# 280049_tester_board.net
KiCad netlist of a schematic drawn in Altium Designer
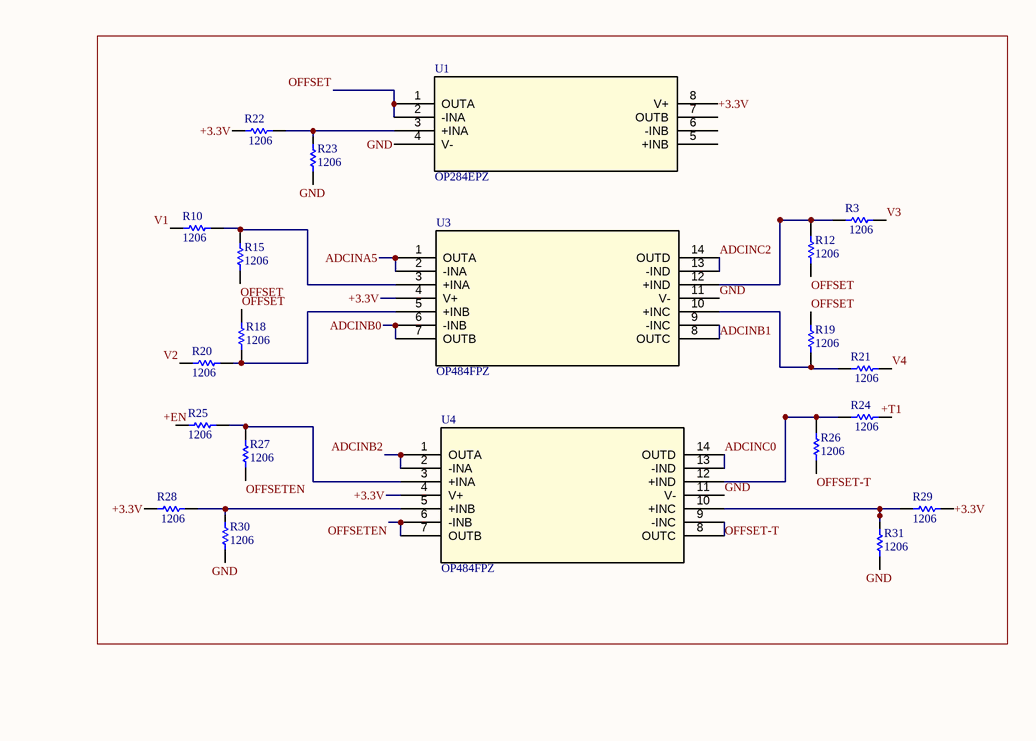
[diagram p0: 280049 tester board.SchDoc, top left]
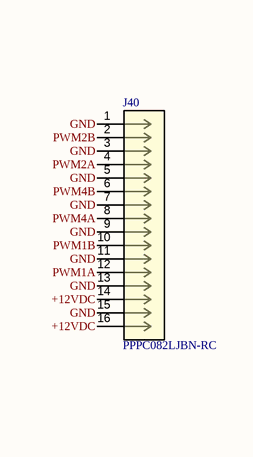
[diagram p1: 280049 tester board.SchDoc, top right]
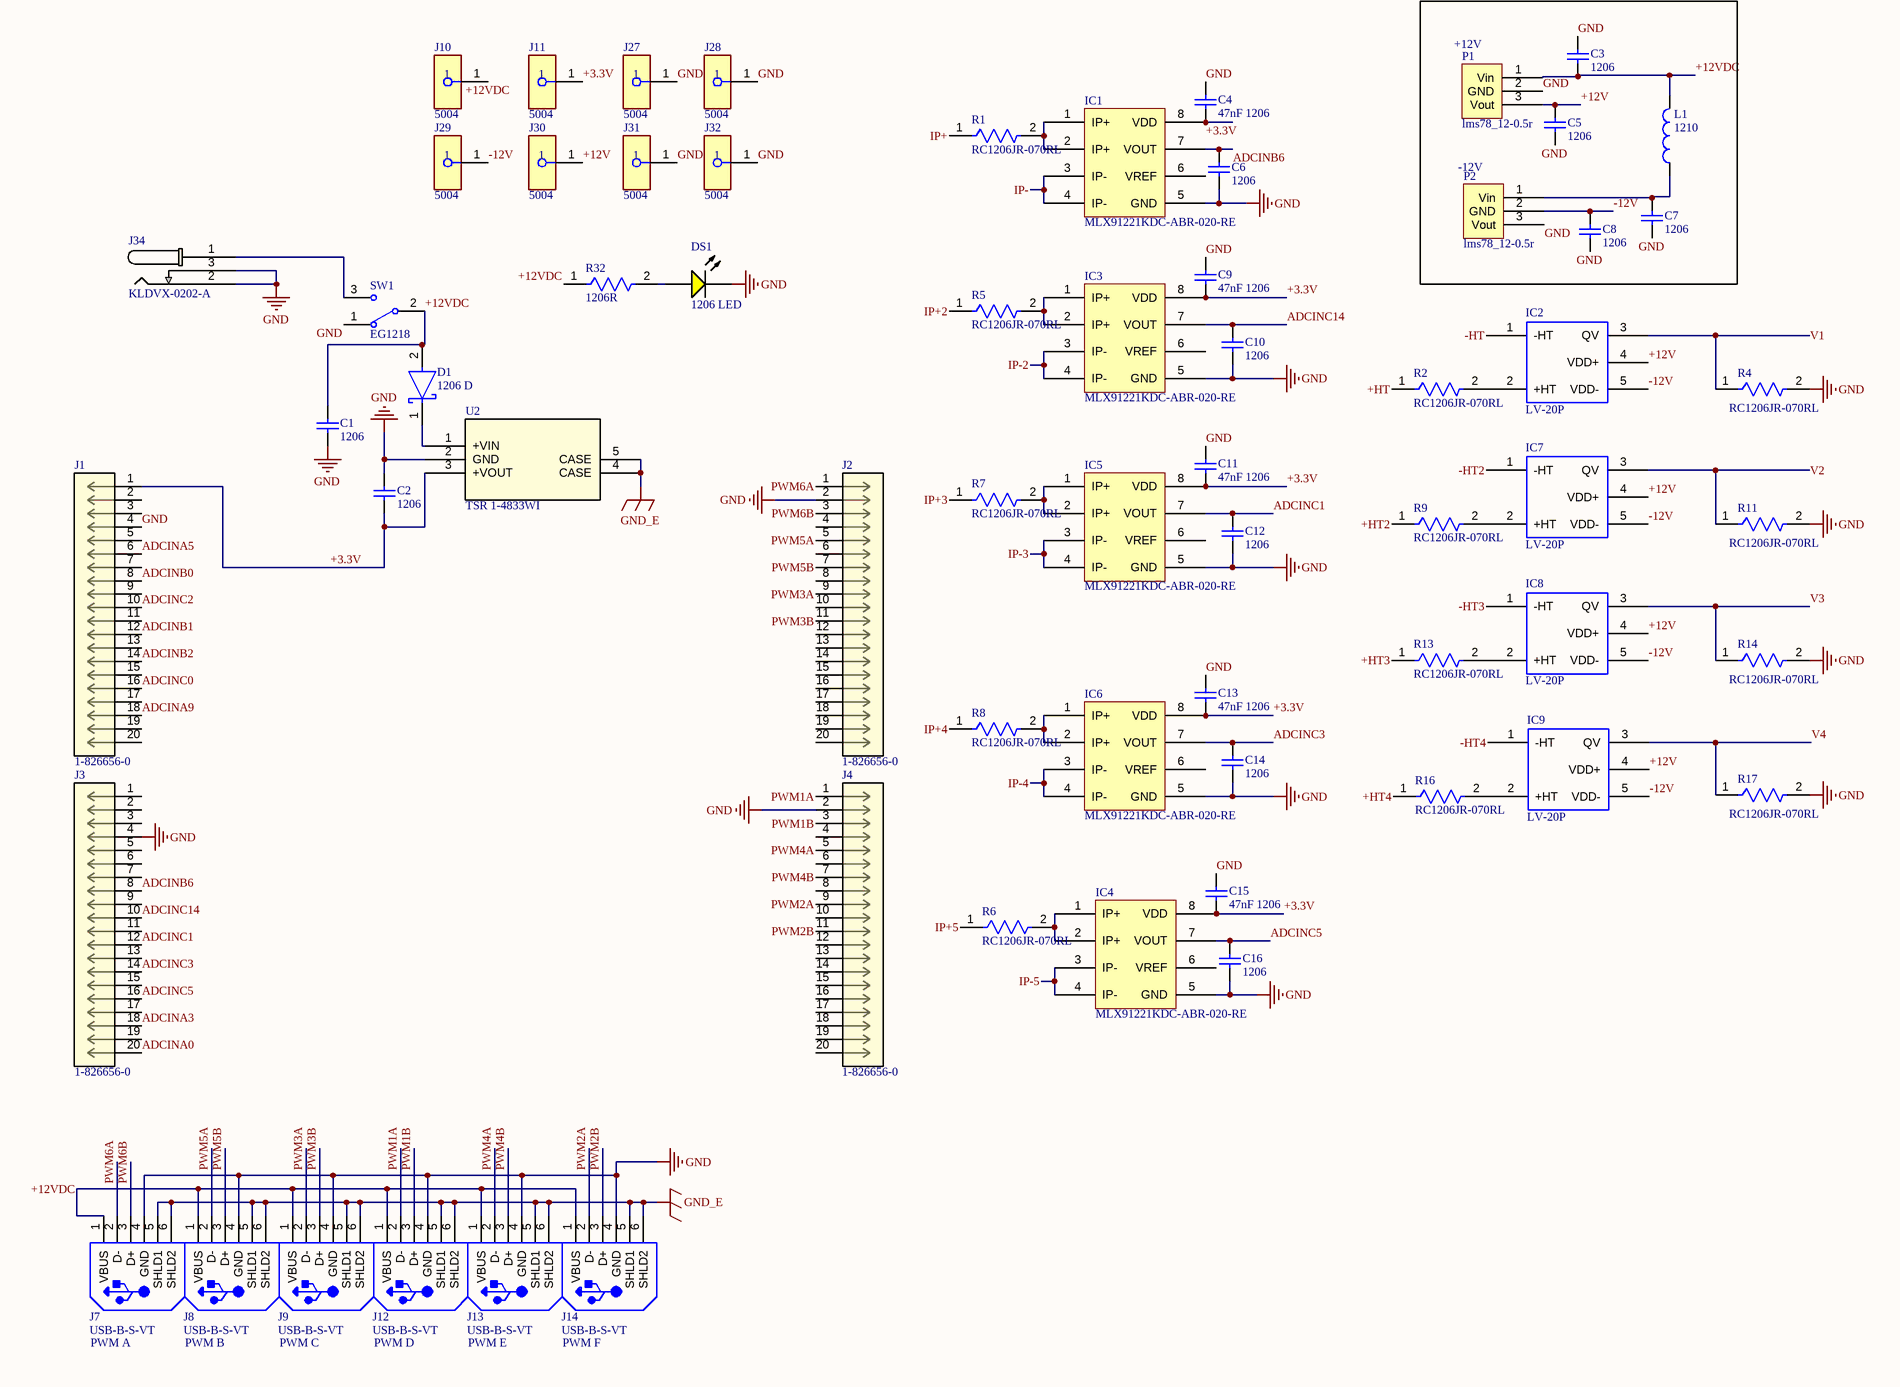
[diagram p2: 280049 tester board.SchDoc, bottom left]
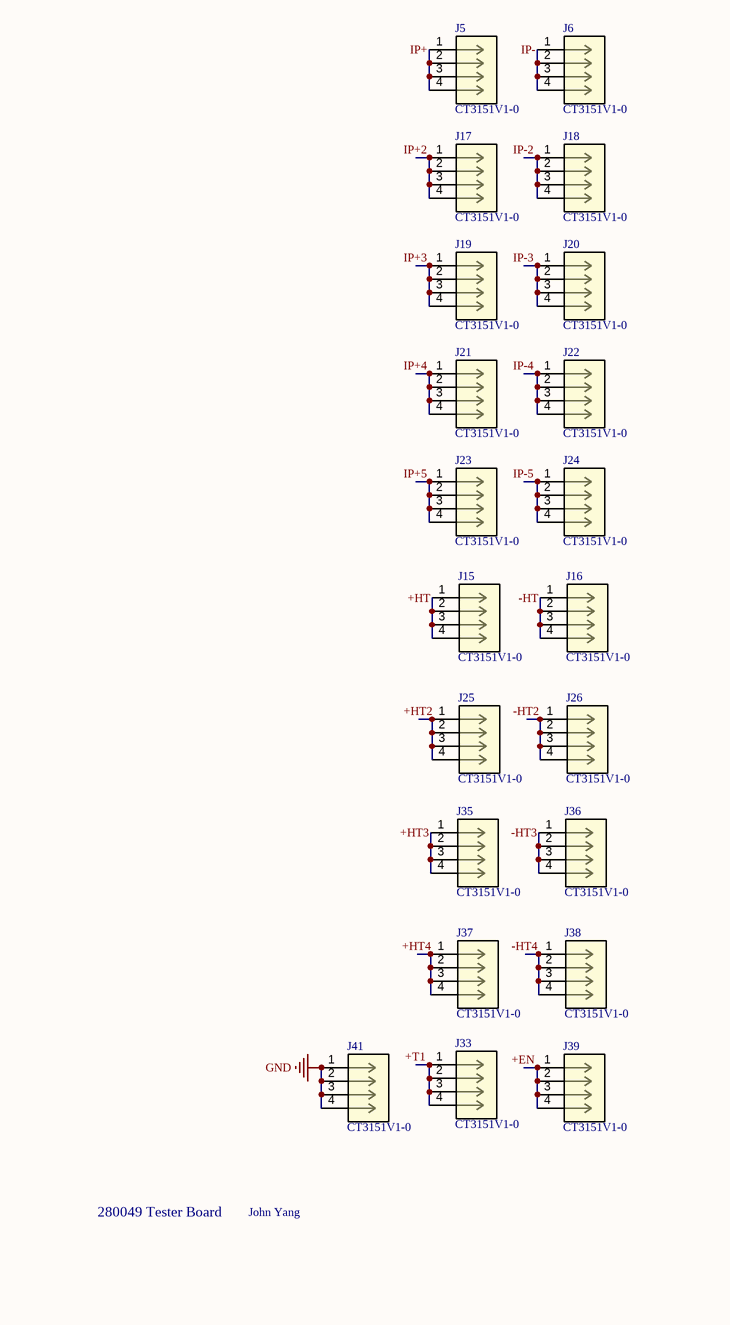
[diagram p3: 280049 tester board.SchDoc, bottom right]

(export (version "E")
  (design (tool "Eeschema 10.0.6"))
  (components
    (comp (ref "C1")
      (value "1206")
      (footprint "CAPC1206(3216)130_M")
      (description "CAP 47nF 200V ±10% 1206 (3216 Metric) Thickness 1.3mm SMD")
      (fields (field (name "TOLERANCE") "Â±10%"))
      (libsource (lib "Altium Content Vault") (part "CAP"))
    )
    (comp (ref "C2")
      (value "1206")
      (footprint "CAPC1206(3216)130_M")
      (description "CAP 47nF 200V ±10% 1206 (3216 Metric) Thickness 1.3mm SMD")
      (fields (field (name "TOLERANCE") "Â±10%"))
      (libsource (lib "Altium Content Vault") (part "CAP"))
    )
    (comp (ref "C3")
      (value "1206")
      (footprint "CAPC1206(3216)130_M")
      (description "CAP 47nF 200V ±10% 1206 (3216 Metric) Thickness 1.3mm SMD")
      (fields (field (name "TOLERANCE") "Â±10%"))
      (libsource (lib "Altium Content Vault") (part "CAP"))
    )
    (comp (ref "C4")
      (value "47nF 1206")
      (footprint "CAPC1206(3216)130_M")
      (description "CAP 47nF 200V ±10% 1206 (3216 Metric) Thickness 1.3mm SMD")
      (fields (field (name "TOLERANCE") "Â±10%"))
      (libsource (lib "Altium Content Vault") (part "CAP"))
    )
    (comp (ref "C5")
      (value "1206")
      (footprint "CAPC1206(3216)130_M")
      (description "CAP 47nF 200V ±10% 1206 (3216 Metric) Thickness 1.3mm SMD")
      (fields (field (name "TOLERANCE") "Â±10%"))
      (libsource (lib "Altium Content Vault") (part "CAP"))
    )
    (comp (ref "C6")
      (value "1206")
      (footprint "CAPC1206(3216)130_M")
      (description "CAP 47nF 200V ±10% 1206 (3216 Metric) Thickness 1.3mm SMD")
      (fields (field (name "TOLERANCE") "Â±10%"))
      (libsource (lib "Altium Content Vault") (part "CAP"))
    )
    (comp (ref "C7")
      (value "1206")
      (footprint "CAPC1206(3216)130_M")
      (description "CAP 47nF 200V ±10% 1206 (3216 Metric) Thickness 1.3mm SMD")
      (fields (field (name "TOLERANCE") "Â±10%"))
      (libsource (lib "Altium Content Vault") (part "CAP"))
    )
    (comp (ref "C8")
      (value "1206")
      (footprint "CAPC1206(3216)130_M")
      (description "CAP 47nF 200V ±10% 1206 (3216 Metric) Thickness 1.3mm SMD")
      (fields (field (name "TOLERANCE") "Â±10%"))
      (libsource (lib "Altium Content Vault") (part "CAP"))
    )
    (comp (ref "C9")
      (value "47nF 1206")
      (footprint "CAPC1206(3216)130_M")
      (description "CAP 47nF 200V ±10% 1206 (3216 Metric) Thickness 1.3mm SMD")
      (fields (field (name "TOLERANCE") "Â±10%"))
      (libsource (lib "Altium Content Vault") (part "CAP"))
    )
    (comp (ref "C10")
      (value "1206")
      (footprint "CAPC1206(3216)130_M")
      (description "CAP 47nF 200V ±10% 1206 (3216 Metric) Thickness 1.3mm SMD")
      (fields (field (name "TOLERANCE") "Â±10%"))
      (libsource (lib "Altium Content Vault") (part "CAP"))
    )
    (comp (ref "C11")
      (value "47nF 1206")
      (footprint "CAPC1206(3216)130_M")
      (description "CAP 47nF 200V ±10% 1206 (3216 Metric) Thickness 1.3mm SMD")
      (fields (field (name "TOLERANCE") "Â±10%"))
      (libsource (lib "Altium Content Vault") (part "CAP"))
    )
    (comp (ref "C12")
      (value "1206")
      (footprint "CAPC1206(3216)130_M")
      (description "CAP 47nF 200V ±10% 1206 (3216 Metric) Thickness 1.3mm SMD")
      (fields (field (name "TOLERANCE") "Â±10%"))
      (libsource (lib "Altium Content Vault") (part "CAP"))
    )
    (comp (ref "C13")
      (value "47nF 1206")
      (footprint "CAPC1206(3216)130_M")
      (description "CAP 47nF 200V ±10% 1206 (3216 Metric) Thickness 1.3mm SMD")
      (fields (field (name "TOLERANCE") "Â±10%"))
      (libsource (lib "Altium Content Vault") (part "CAP"))
    )
    (comp (ref "C14")
      (value "1206")
      (footprint "CAPC1206(3216)130_M")
      (description "CAP 47nF 200V ±10% 1206 (3216 Metric) Thickness 1.3mm SMD")
      (fields (field (name "TOLERANCE") "Â±10%"))
      (libsource (lib "Altium Content Vault") (part "CAP"))
    )
    (comp (ref "C15")
      (value "47nF 1206")
      (footprint "CAPC1206(3216)130_M")
      (description "CAP 47nF 200V ±10% 1206 (3216 Metric) Thickness 1.3mm SMD")
      (fields (field (name "TOLERANCE") "Â±10%"))
      (libsource (lib "Altium Content Vault") (part "CAP"))
    )
    (comp (ref "C16")
      (value "1206")
      (footprint "CAPC1206(3216)130_M")
      (description "CAP 47nF 200V ±10% 1206 (3216 Metric) Thickness 1.3mm SMD")
      (fields (field (name "TOLERANCE") "Â±10%"))
      (libsource (lib "Altium Content Vault") (part "CAP"))
    )
    (comp (ref "D1")
      (value "1206 D")
      (footprint "FP-SD1206S-MFG")
      (description "DIODE SCHOTTKY 40V 2A 1206")
      (fields (field (name "MANUFACTURER PART NUMBER") "SD1206S040S2R0") (field (name "MANUFACTURER") "AVX"))
      (libsource (lib "Altium Content Vault") (part "1d6ec82d83fb6aee721767c19dac4b9"))
    )
    (comp (ref "DS1")
      (value "1206 LED")
      (footprint "LUMX-SML-LX1206YC-TR_V")
      (description "Yellow LED, Water Clear Len, 585 nm, 2.1 V, -40 to 85 degC, 2-Pin SMD, RoHS, Tape and Reel")
      (fields (field (name "MANUFACTURER") "Lumex"))
      (libsource (lib "Altium Content Vault") (part "LED-YELLOW-AK-2"))
    )
    (comp (ref "IC1")
      (value "MLX91221KDC-ABR-020-RE")
      (footprint "MLX91221KDC-ABR-020-RE")
      (description ".088 W")
      (libsource (lib "John Yang") (part "MLX91221KDC-ABR-020-RE"))
    )
    (comp (ref "IC2")
      (value "LV-20P")
      (footprint "LV-20P")
      (description "0.15 W")
      (libsource (lib "LV-20P") (part "LV-20P"))
    )
    (comp (ref "IC3")
      (value "MLX91221KDC-ABR-020-RE")
      (footprint "MLX91221KDC-ABR-020-RE")
      (description ".088 W")
      (libsource (lib "John Yang") (part "MLX91221KDC-ABR-020-RE"))
    )
    (comp (ref "IC4")
      (value "MLX91221KDC-ABR-020-RE")
      (footprint "MLX91221KDC-ABR-020-RE")
      (description ".088 W")
      (libsource (lib "John Yang") (part "MLX91221KDC-ABR-020-RE"))
    )
    (comp (ref "IC5")
      (value "MLX91221KDC-ABR-020-RE")
      (footprint "MLX91221KDC-ABR-020-RE")
      (description ".088 W")
      (libsource (lib "John Yang") (part "MLX91221KDC-ABR-020-RE"))
    )
    (comp (ref "IC6")
      (value "MLX91221KDC-ABR-020-RE")
      (footprint "MLX91221KDC-ABR-020-RE")
      (description ".088 W")
      (libsource (lib "John Yang") (part "MLX91221KDC-ABR-020-RE"))
    )
    (comp (ref "IC7")
      (value "LV-20P")
      (footprint "LV-20P")
      (description "0.15 W")
      (libsource (lib "LV-20P") (part "LV-20P"))
    )
    (comp (ref "IC8")
      (value "LV-20P")
      (footprint "LV-20P")
      (description "0.15 W")
      (libsource (lib "LV-20P") (part "LV-20P"))
    )
    (comp (ref "IC9")
      (value "LV-20P")
      (footprint "LV-20P")
      (description "0.15 W")
      (libsource (lib "LV-20P") (part "LV-20P"))
    )
    (comp (ref "J1")
      (value "1-826656-0")
      (footprint "CON20_2X10_P100UM_HDR_TYC")
      (description "No Description Available")
      (libsource (lib "John Yang") (part "1-826656-0"))
    )
    (comp (ref "J2")
      (value "1-826656-0")
      (footprint "CON20_2X10_P100UM_HDR_TYC")
      (description "No Description Available")
      (libsource (lib "John Yang") (part "1-826656-0"))
    )
    (comp (ref "J3")
      (value "1-826656-0")
      (footprint "CON20_2X10_P100UM_HDR_TYC")
      (description "No Description Available")
      (libsource (lib "John Yang") (part "1-826656-0"))
    )
    (comp (ref "J4")
      (value "1-826656-0")
      (footprint "CON20_2X10_P100UM_HDR_TYC")
      (description "No Description Available")
      (libsource (lib "John Yang") (part "1-826656-0"))
    )
    (comp (ref "J5")
      (value "CT3151V1-0")
      (footprint "CON4_CT3151V1-0_CTE")
      (description "No Description Available")
      (fields (field (name "COPYRIGHT") "Copyright (C) 2024 Ultra Librarian. All rights reserved."))
      (libsource (lib "John Yang") (part "CT3151V1-0"))
    )
    (comp (ref "J6")
      (value "CT3151V1-0")
      (footprint "CON4_CT3151V1-0_CTE")
      (description "No Description Available")
      (fields (field (name "COPYRIGHT") "Copyright (C) 2024 Ultra Librarian. All rights reserved."))
      (libsource (lib "John Yang") (part "CT3151V1-0"))
    )
    (comp (ref "J7")
      (value "PWM A")
      (footprint "CONN4_5787834-1_TEC")
      (description "USB TYPE B SINGLE VERTICAL")
      (fields (field (name "MANUFACTURER") "Adam Tech") (field (name "SUPPLIER PART NUMBER 1") "USB-B-S-VT"))
      (libsource (lib "ECE 512 Breadboard Modular system") (part "CONN_USB_TypeB"))
    )
    (comp (ref "J8")
      (value "PWM B")
      (footprint "CONN4_5787834-1_TEC")
      (description "USB TYPE B SINGLE VERTICAL")
      (fields (field (name "MANUFACTURER") "Adam Tech") (field (name "SUPPLIER PART NUMBER 1") "USB-B-S-VT"))
      (libsource (lib "ECE 512 Breadboard Modular system") (part "CONN_USB_TypeB"))
    )
    (comp (ref "J9")
      (value "PWM C")
      (footprint "CONN4_5787834-1_TEC")
      (description "USB TYPE B SINGLE VERTICAL")
      (fields (field (name "MANUFACTURER") "Adam Tech") (field (name "SUPPLIER PART NUMBER 1") "USB-B-S-VT"))
      (libsource (lib "ECE 512 Breadboard Modular system") (part "CONN_USB_TypeB"))
    )
    (comp (ref "J10")
      (value "5004")
      (footprint "FP-5004-MFG")
      (description "PC TEST POINT MINIATURE YELLOW")
      (fields
        (field (name "MANUFACTURER") "Keystone")
        (field (name "OCTOPART") "https://octopart.com/5004-keystone-28591")
      )
      (libsource (lib "Altium Content Vault") (part "98815daf2f2c152b0c43f5ab9800df6"))
    )
    (comp (ref "J11")
      (value "5004")
      (footprint "FP-5004-MFG")
      (description "PC TEST POINT MINIATURE YELLOW")
      (fields
        (field (name "MANUFACTURER") "Keystone")
        (field (name "OCTOPART") "https://octopart.com/5004-keystone-28591")
      )
      (libsource (lib "Altium Content Vault") (part "98815daf2f2c152b0c43f5ab9800df6"))
    )
    (comp (ref "J12")
      (value "PWM D")
      (footprint "CONN4_5787834-1_TEC")
      (description "USB TYPE B SINGLE VERTICAL")
      (fields (field (name "MANUFACTURER") "Adam Tech") (field (name "SUPPLIER PART NUMBER 1") "USB-B-S-VT"))
      (libsource (lib "ECE 512 Breadboard Modular system") (part "CONN_USB_TypeB"))
    )
    (comp (ref "J13")
      (value "PWM E")
      (footprint "CONN4_5787834-1_TEC")
      (description "USB TYPE B SINGLE VERTICAL")
      (fields (field (name "MANUFACTURER") "Adam Tech") (field (name "SUPPLIER PART NUMBER 1") "USB-B-S-VT"))
      (libsource (lib "ECE 512 Breadboard Modular system") (part "CONN_USB_TypeB"))
    )
    (comp (ref "J14")
      (value "PWM F")
      (footprint "CONN4_5787834-1_TEC")
      (description "USB TYPE B SINGLE VERTICAL")
      (fields (field (name "MANUFACTURER") "Adam Tech") (field (name "SUPPLIER PART NUMBER 1") "USB-B-S-VT"))
      (libsource (lib "ECE 512 Breadboard Modular system") (part "CONN_USB_TypeB"))
    )
    (comp (ref "J15")
      (value "CT3151V1-0")
      (footprint "CON4_CT3151V1-0_CTE")
      (description "No Description Available")
      (fields (field (name "COPYRIGHT") "Copyright (C) 2024 Ultra Librarian. All rights reserved."))
      (libsource (lib "John Yang") (part "CT3151V1-0"))
    )
    (comp (ref "J16")
      (value "CT3151V1-0")
      (footprint "CON4_CT3151V1-0_CTE")
      (description "No Description Available")
      (fields (field (name "COPYRIGHT") "Copyright (C) 2024 Ultra Librarian. All rights reserved."))
      (libsource (lib "John Yang") (part "CT3151V1-0"))
    )
    (comp (ref "J17")
      (value "CT3151V1-0")
      (footprint "CON4_CT3151V1-0_CTE")
      (description "No Description Available")
      (fields (field (name "COPYRIGHT") "Copyright (C) 2024 Ultra Librarian. All rights reserved."))
      (libsource (lib "John Yang") (part "CT3151V1-0"))
    )
    (comp (ref "J18")
      (value "CT3151V1-0")
      (footprint "CON4_CT3151V1-0_CTE")
      (description "No Description Available")
      (fields (field (name "COPYRIGHT") "Copyright (C) 2024 Ultra Librarian. All rights reserved."))
      (libsource (lib "John Yang") (part "CT3151V1-0"))
    )
    (comp (ref "J19")
      (value "CT3151V1-0")
      (footprint "CON4_CT3151V1-0_CTE")
      (description "No Description Available")
      (fields (field (name "COPYRIGHT") "Copyright (C) 2024 Ultra Librarian. All rights reserved."))
      (libsource (lib "John Yang") (part "CT3151V1-0"))
    )
    (comp (ref "J20")
      (value "CT3151V1-0")
      (footprint "CON4_CT3151V1-0_CTE")
      (description "No Description Available")
      (fields (field (name "COPYRIGHT") "Copyright (C) 2024 Ultra Librarian. All rights reserved."))
      (libsource (lib "John Yang") (part "CT3151V1-0"))
    )
    (comp (ref "J21")
      (value "CT3151V1-0")
      (footprint "CON4_CT3151V1-0_CTE")
      (description "No Description Available")
      (fields (field (name "COPYRIGHT") "Copyright (C) 2024 Ultra Librarian. All rights reserved."))
      (libsource (lib "John Yang") (part "CT3151V1-0"))
    )
    (comp (ref "J22")
      (value "CT3151V1-0")
      (footprint "CON4_CT3151V1-0_CTE")
      (description "No Description Available")
      (fields (field (name "COPYRIGHT") "Copyright (C) 2024 Ultra Librarian. All rights reserved."))
      (libsource (lib "John Yang") (part "CT3151V1-0"))
    )
    (comp (ref "J23")
      (value "CT3151V1-0")
      (footprint "CON4_CT3151V1-0_CTE")
      (description "No Description Available")
      (fields (field (name "COPYRIGHT") "Copyright (C) 2024 Ultra Librarian. All rights reserved."))
      (libsource (lib "John Yang") (part "CT3151V1-0"))
    )
    (comp (ref "J24")
      (value "CT3151V1-0")
      (footprint "CON4_CT3151V1-0_CTE")
      (description "No Description Available")
      (fields (field (name "COPYRIGHT") "Copyright (C) 2024 Ultra Librarian. All rights reserved."))
      (libsource (lib "John Yang") (part "CT3151V1-0"))
    )
    (comp (ref "J25")
      (value "CT3151V1-0")
      (footprint "CON4_CT3151V1-0_CTE")
      (description "No Description Available")
      (fields (field (name "COPYRIGHT") "Copyright (C) 2024 Ultra Librarian. All rights reserved."))
      (libsource (lib "John Yang") (part "CT3151V1-0"))
    )
    (comp (ref "J26")
      (value "CT3151V1-0")
      (footprint "CON4_CT3151V1-0_CTE")
      (description "No Description Available")
      (fields (field (name "COPYRIGHT") "Copyright (C) 2024 Ultra Librarian. All rights reserved."))
      (libsource (lib "John Yang") (part "CT3151V1-0"))
    )
    (comp (ref "J27")
      (value "5004")
      (footprint "FP-5004-MFG")
      (description "PC TEST POINT MINIATURE YELLOW")
      (fields
        (field (name "MANUFACTURER") "Keystone")
        (field (name "OCTOPART") "https://octopart.com/5004-keystone-28591")
      )
      (libsource (lib "Altium Content Vault") (part "98815daf2f2c152b0c43f5ab9800df6"))
    )
    (comp (ref "J28")
      (value "5004")
      (footprint "FP-5004-MFG")
      (description "PC TEST POINT MINIATURE YELLOW")
      (fields
        (field (name "MANUFACTURER") "Keystone")
        (field (name "OCTOPART") "https://octopart.com/5004-keystone-28591")
      )
      (libsource (lib "Altium Content Vault") (part "98815daf2f2c152b0c43f5ab9800df6"))
    )
    (comp (ref "J29")
      (value "5004")
      (footprint "FP-5004-MFG")
      (description "PC TEST POINT MINIATURE YELLOW")
      (fields
        (field (name "MANUFACTURER") "Keystone")
        (field (name "OCTOPART") "https://octopart.com/5004-keystone-28591")
      )
      (libsource (lib "Altium Content Vault") (part "98815daf2f2c152b0c43f5ab9800df6"))
    )
    (comp (ref "J30")
      (value "5004")
      (footprint "FP-5004-MFG")
      (description "PC TEST POINT MINIATURE YELLOW")
      (fields
        (field (name "MANUFACTURER") "Keystone")
        (field (name "OCTOPART") "https://octopart.com/5004-keystone-28591")
      )
      (libsource (lib "Altium Content Vault") (part "98815daf2f2c152b0c43f5ab9800df6"))
    )
    (comp (ref "J31")
      (value "5004")
      (footprint "FP-5004-MFG")
      (description "PC TEST POINT MINIATURE YELLOW")
      (fields
        (field (name "MANUFACTURER") "Keystone")
        (field (name "OCTOPART") "https://octopart.com/5004-keystone-28591")
      )
      (libsource (lib "Altium Content Vault") (part "98815daf2f2c152b0c43f5ab9800df6"))
    )
    (comp (ref "J32")
      (value "5004")
      (footprint "FP-5004-MFG")
      (description "PC TEST POINT MINIATURE YELLOW")
      (fields
        (field (name "MANUFACTURER") "Keystone")
        (field (name "OCTOPART") "https://octopart.com/5004-keystone-28591")
      )
      (libsource (lib "Altium Content Vault") (part "98815daf2f2c152b0c43f5ab9800df6"))
    )
    (comp (ref "J33")
      (value "CT3151V1-0")
      (footprint "CON4_CT3151V1-0_CTE")
      (description "No Description Available")
      (fields (field (name "COPYRIGHT") "Copyright (C) 2024 Ultra Librarian. All rights reserved."))
      (libsource (lib "John Yang") (part "CT3151V1-0"))
    )
    (comp (ref "J34")
      (value "KLDVX-0202-A")
      (footprint "JACK_KLDVX-0202_KYC")
      (description "No Description Available")
      (libsource (lib "KLDVX-0202-A") (part "KLDVX-0202-A"))
    )
    (comp (ref "J35")
      (value "CT3151V1-0")
      (footprint "CON4_CT3151V1-0_CTE")
      (description "No Description Available")
      (fields (field (name "COPYRIGHT") "Copyright (C) 2024 Ultra Librarian. All rights reserved."))
      (libsource (lib "John Yang") (part "CT3151V1-0"))
    )
    (comp (ref "J36")
      (value "CT3151V1-0")
      (footprint "CON4_CT3151V1-0_CTE")
      (description "No Description Available")
      (fields (field (name "COPYRIGHT") "Copyright (C) 2024 Ultra Librarian. All rights reserved."))
      (libsource (lib "John Yang") (part "CT3151V1-0"))
    )
    (comp (ref "J37")
      (value "CT3151V1-0")
      (footprint "CON4_CT3151V1-0_CTE")
      (description "No Description Available")
      (fields (field (name "COPYRIGHT") "Copyright (C) 2024 Ultra Librarian. All rights reserved."))
      (libsource (lib "John Yang") (part "CT3151V1-0"))
    )
    (comp (ref "J38")
      (value "CT3151V1-0")
      (footprint "CON4_CT3151V1-0_CTE")
      (description "No Description Available")
      (fields (field (name "COPYRIGHT") "Copyright (C) 2024 Ultra Librarian. All rights reserved."))
      (libsource (lib "John Yang") (part "CT3151V1-0"))
    )
    (comp (ref "J39")
      (value "CT3151V1-0")
      (footprint "CON4_CT3151V1-0_CTE")
      (description "No Description Available")
      (fields (field (name "COPYRIGHT") "Copyright (C) 2024 Ultra Librarian. All rights reserved."))
      (libsource (lib "John Yang") (part "CT3151V1-0"))
    )
    (comp (ref "J40")
      (value "PPPC082LJBN-RC")
      (footprint "CONN_PPPC082LJBN-RC_SUL")
      (description "No Description Available")
      (libsource (lib "PPPC082LJBN-RC") (part "PPPC082LJBN-RC"))
    )
    (comp (ref "J41")
      (value "CT3151V1-0")
      (footprint "CON4_CT3151V1-0_CTE")
      (description "No Description Available")
      (fields (field (name "COPYRIGHT") "Copyright (C) 2024 Ultra Librarian. All rights reserved."))
      (libsource (lib "John Yang") (part "CT3151V1-0"))
    )
    (comp (ref "L1")
      (value "1210")
      (footprint "TDK-NLV32-PF_V")
      (description "Wire Wound Inductor, 1 uH, +/- 5%, -40 to 105 degC, 2-Pin Molded, RoHS, Tape and Reel")
      (fields (field (name "MANUFACTURER") "TDK") (field (name "TOLERANCE") "±5%"))
      (libsource (lib "Altium Content Vault") (part "IND-2"))
    )
    (comp (ref "P1")
      (value "lms78_12-0.5r")
      (footprint "lms78_12-0.5r")
      (libsource (lib "LV-20P") (part "lms78_12-0.5r"))
    )
    (comp (ref "P2")
      (value "lms78_12-0.5r")
      (footprint "lms78_12-0.5r")
      (libsource (lib "LV-20P") (part "lms78_12-0.5r"))
    )
    (comp (ref "R1")
      (value "RC1206JR-070RL")
      (footprint "FP-RC1206-MFG")
      (description "RES SMD 0 OHM JUMPER 1/4W 1206")
      (fields
        (field (name "MANUFACTURER") "YAGEO")
        (field (name "OCTOPART") "https://octopart.com/rc1206jr-070rl-yageo-40025601")
      )
      (libsource (lib "Altium Content Vault") (part "1029c3af85768c4190bb7ad29bc67b5"))
    )
    (comp (ref "R2")
      (value "RC1206JR-070RL")
      (footprint "FP-RC1206-MFG")
      (description "RES SMD 0 OHM JUMPER 1/4W 1206")
      (fields
        (field (name "MANUFACTURER") "YAGEO")
        (field (name "OCTOPART") "https://octopart.com/rc1206jr-070rl-yageo-40025601")
      )
      (libsource (lib "Altium Content Vault") (part "1029c3af85768c4190bb7ad29bc67b5"))
    )
    (comp (ref "R3")
      (value "1206")
      (footprint "RESC3216X70X50NL05T20")
      (fields (field (name "MANUFACTURER") "Panasonic") (field (name "PART NUMBER") "ERJ-8GEY0R00V"))
      (libsource (lib "Altium Content Vault") (part "RES"))
    )
    (comp (ref "R4")
      (value "RC1206JR-070RL")
      (footprint "FP-RC1206-MFG")
      (description "RES SMD 0 OHM JUMPER 1/4W 1206")
      (fields
        (field (name "MANUFACTURER") "YAGEO")
        (field (name "OCTOPART") "https://octopart.com/rc1206jr-070rl-yageo-40025601")
      )
      (libsource (lib "Altium Content Vault") (part "1029c3af85768c4190bb7ad29bc67b5"))
    )
    (comp (ref "R5")
      (value "RC1206JR-070RL")
      (footprint "FP-RC1206-MFG")
      (description "RES SMD 0 OHM JUMPER 1/4W 1206")
      (fields
        (field (name "MANUFACTURER") "YAGEO")
        (field (name "OCTOPART") "https://octopart.com/rc1206jr-070rl-yageo-40025601")
      )
      (libsource (lib "Altium Content Vault") (part "1029c3af85768c4190bb7ad29bc67b5"))
    )
    (comp (ref "R6")
      (value "RC1206JR-070RL")
      (footprint "FP-RC1206-MFG")
      (description "RES SMD 0 OHM JUMPER 1/4W 1206")
      (fields
        (field (name "MANUFACTURER") "YAGEO")
        (field (name "OCTOPART") "https://octopart.com/rc1206jr-070rl-yageo-40025601")
      )
      (libsource (lib "Altium Content Vault") (part "1029c3af85768c4190bb7ad29bc67b5"))
    )
    (comp (ref "R7")
      (value "RC1206JR-070RL")
      (footprint "FP-RC1206-MFG")
      (description "RES SMD 0 OHM JUMPER 1/4W 1206")
      (fields
        (field (name "MANUFACTURER") "YAGEO")
        (field (name "OCTOPART") "https://octopart.com/rc1206jr-070rl-yageo-40025601")
      )
      (libsource (lib "Altium Content Vault") (part "1029c3af85768c4190bb7ad29bc67b5"))
    )
    (comp (ref "R8")
      (value "RC1206JR-070RL")
      (footprint "FP-RC1206-MFG")
      (description "RES SMD 0 OHM JUMPER 1/4W 1206")
      (fields
        (field (name "MANUFACTURER") "YAGEO")
        (field (name "OCTOPART") "https://octopart.com/rc1206jr-070rl-yageo-40025601")
      )
      (libsource (lib "Altium Content Vault") (part "1029c3af85768c4190bb7ad29bc67b5"))
    )
    (comp (ref "R9")
      (value "RC1206JR-070RL")
      (footprint "FP-RC1206-MFG")
      (description "RES SMD 0 OHM JUMPER 1/4W 1206")
      (fields
        (field (name "MANUFACTURER") "YAGEO")
        (field (name "OCTOPART") "https://octopart.com/rc1206jr-070rl-yageo-40025601")
      )
      (libsource (lib "Altium Content Vault") (part "1029c3af85768c4190bb7ad29bc67b5"))
    )
    (comp (ref "R10")
      (value "1206")
      (footprint "RESC3216X70X50NL05T20")
      (fields (field (name "MANUFACTURER") "Panasonic") (field (name "PART NUMBER") "ERJ-8GEY0R00V"))
      (libsource (lib "Altium Content Vault") (part "RES"))
    )
    (comp (ref "R11")
      (value "RC1206JR-070RL")
      (footprint "FP-RC1206-MFG")
      (description "RES SMD 0 OHM JUMPER 1/4W 1206")
      (fields
        (field (name "MANUFACTURER") "YAGEO")
        (field (name "OCTOPART") "https://octopart.com/rc1206jr-070rl-yageo-40025601")
      )
      (libsource (lib "Altium Content Vault") (part "1029c3af85768c4190bb7ad29bc67b5"))
    )
    (comp (ref "R12")
      (value "1206")
      (footprint "RESC3216X70X50NL05T20")
      (fields (field (name "MANUFACTURER") "Panasonic") (field (name "PART NUMBER") "ERJ-8GEY0R00V"))
      (libsource (lib "Altium Content Vault") (part "RES"))
    )
    (comp (ref "R13")
      (value "RC1206JR-070RL")
      (footprint "FP-RC1206-MFG")
      (description "RES SMD 0 OHM JUMPER 1/4W 1206")
      (fields
        (field (name "MANUFACTURER") "YAGEO")
        (field (name "OCTOPART") "https://octopart.com/rc1206jr-070rl-yageo-40025601")
      )
      (libsource (lib "Altium Content Vault") (part "1029c3af85768c4190bb7ad29bc67b5"))
    )
    (comp (ref "R14")
      (value "RC1206JR-070RL")
      (footprint "FP-RC1206-MFG")
      (description "RES SMD 0 OHM JUMPER 1/4W 1206")
      (fields
        (field (name "MANUFACTURER") "YAGEO")
        (field (name "OCTOPART") "https://octopart.com/rc1206jr-070rl-yageo-40025601")
      )
      (libsource (lib "Altium Content Vault") (part "1029c3af85768c4190bb7ad29bc67b5"))
    )
    (comp (ref "R15")
      (value "1206")
      (footprint "RESC3216X70X50NL05T20")
      (fields (field (name "MANUFACTURER") "Panasonic") (field (name "PART NUMBER") "ERJ-8GEY0R00V"))
      (libsource (lib "Altium Content Vault") (part "RES"))
    )
    (comp (ref "R16")
      (value "RC1206JR-070RL")
      (footprint "FP-RC1206-MFG")
      (description "RES SMD 0 OHM JUMPER 1/4W 1206")
      (fields
        (field (name "MANUFACTURER") "YAGEO")
        (field (name "OCTOPART") "https://octopart.com/rc1206jr-070rl-yageo-40025601")
      )
      (libsource (lib "Altium Content Vault") (part "1029c3af85768c4190bb7ad29bc67b5"))
    )
    (comp (ref "R17")
      (value "RC1206JR-070RL")
      (footprint "FP-RC1206-MFG")
      (description "RES SMD 0 OHM JUMPER 1/4W 1206")
      (fields
        (field (name "MANUFACTURER") "YAGEO")
        (field (name "OCTOPART") "https://octopart.com/rc1206jr-070rl-yageo-40025601")
      )
      (libsource (lib "Altium Content Vault") (part "1029c3af85768c4190bb7ad29bc67b5"))
    )
    (comp (ref "R18")
      (value "1206")
      (footprint "RESC3216X70X50NL05T20")
      (fields (field (name "MANUFACTURER") "Panasonic") (field (name "PART NUMBER") "ERJ-8GEY0R00V"))
      (libsource (lib "Altium Content Vault") (part "RES"))
    )
    (comp (ref "R19")
      (value "1206")
      (footprint "RESC3216X70X50NL05T20")
      (fields (field (name "MANUFACTURER") "Panasonic") (field (name "PART NUMBER") "ERJ-8GEY0R00V"))
      (libsource (lib "Altium Content Vault") (part "RES"))
    )
    (comp (ref "R20")
      (value "1206")
      (footprint "RESC3216X70X50NL05T20")
      (fields (field (name "MANUFACTURER") "Panasonic") (field (name "PART NUMBER") "ERJ-8GEY0R00V"))
      (libsource (lib "Altium Content Vault") (part "RES"))
    )
    (comp (ref "R21")
      (value "1206")
      (footprint "RESC3216X70X50NL05T20")
      (fields (field (name "MANUFACTURER") "Panasonic") (field (name "PART NUMBER") "ERJ-8GEY0R00V"))
      (libsource (lib "Altium Content Vault") (part "RES"))
    )
    (comp (ref "R22")
      (value "1206")
      (footprint "RESC3216X70X50NL05T20")
      (fields (field (name "MANUFACTURER") "Panasonic") (field (name "PART NUMBER") "ERJ-8GEY0R00V"))
      (libsource (lib "Altium Content Vault") (part "RES"))
    )
    (comp (ref "R23")
      (value "1206")
      (footprint "RESC3216X70X50NL05T20")
      (fields (field (name "MANUFACTURER") "Panasonic") (field (name "PART NUMBER") "ERJ-8GEY0R00V"))
      (libsource (lib "Altium Content Vault") (part "RES"))
    )
    (comp (ref "R24")
      (value "1206")
      (footprint "RESC3216X70X50NL05T20")
      (fields (field (name "MANUFACTURER") "Panasonic") (field (name "PART NUMBER") "ERJ-8GEY0R00V"))
      (libsource (lib "Altium Content Vault") (part "RES"))
    )
    (comp (ref "R25")
      (value "1206")
      (footprint "RESC3216X70X50NL05T20")
      (fields (field (name "MANUFACTURER") "Panasonic") (field (name "PART NUMBER") "ERJ-8GEY0R00V"))
      (libsource (lib "Altium Content Vault") (part "RES"))
    )
    (comp (ref "R26")
      (value "1206")
      (footprint "RESC3216X70X50NL05T20")
      (fields (field (name "MANUFACTURER") "Panasonic") (field (name "PART NUMBER") "ERJ-8GEY0R00V"))
      (libsource (lib "Altium Content Vault") (part "RES"))
    )
    (comp (ref "R27")
      (value "1206")
      (footprint "RESC3216X70X50NL05T20")
      (fields (field (name "MANUFACTURER") "Panasonic") (field (name "PART NUMBER") "ERJ-8GEY0R00V"))
      (libsource (lib "Altium Content Vault") (part "RES"))
    )
    (comp (ref "R28")
      (value "1206")
      (footprint "RESC3216X70X50NL05T20")
      (fields (field (name "MANUFACTURER") "Panasonic") (field (name "PART NUMBER") "ERJ-8GEY0R00V"))
      (libsource (lib "Altium Content Vault") (part "RES"))
    )
    (comp (ref "R29")
      (value "1206")
      (footprint "RESC3216X70X50NL05T20")
      (fields (field (name "MANUFACTURER") "Panasonic") (field (name "PART NUMBER") "ERJ-8GEY0R00V"))
      (libsource (lib "Altium Content Vault") (part "RES"))
    )
    (comp (ref "R30")
      (value "1206")
      (footprint "RESC3216X70X50NL05T20")
      (fields (field (name "MANUFACTURER") "Panasonic") (field (name "PART NUMBER") "ERJ-8GEY0R00V"))
      (libsource (lib "Altium Content Vault") (part "RES"))
    )
    (comp (ref "R31")
      (value "1206")
      (footprint "RESC3216X70X50NL05T20")
      (fields (field (name "MANUFACTURER") "Panasonic") (field (name "PART NUMBER") "ERJ-8GEY0R00V"))
      (libsource (lib "Altium Content Vault") (part "RES"))
    )
    (comp (ref "R32")
      (value "1206R")
      (footprint "FP-RC1206-MFG")
      (description "RES SMD 0 OHM JUMPER 1/4W 1206")
      (fields
        (field (name "MANUFACTURER PART NUMBER") "RC1206JR-070RL")
        (field (name "MANUFACTURER") "YAGEO")
      )
      (libsource (lib "Altium Content Vault") (part "1029c3af85768c4190bb7ad29bc67b5"))
    )
    (comp (ref "SW1")
      (value "EG1218")
      (footprint "ESWI-EG1218_V")
      (description "Slide Switch, 500 V, -20 to 70 degC, 3-Pin THD, RoHS")
      (libsource (lib "Altium Content Vault") (part "SW-SPDT-3_B"))
    )
    (comp (ref "U1")
      (value "OP284EPZ")
      (footprint "N_8_ADI")
      (description "No Description Available")
      (libsource (lib "OP284EPZ") (part "OP284EPZ"))
    )
    (comp (ref "U2")
      (value "TSR 1-4833WI")
      (footprint "TSR1WI-SINGLE_TRP")
      (description "TSR 1-4833WI DC-DC Converter, POL, Industrial, Encapsulated, 1A, 3.3V Out, 9-72V In")
      (libsource (lib "Altium Content Vault") (part "TSR 1-4833WI"))
    )
    (comp (ref "U3")
      (value "OP484FPZ")
      (footprint "N_14_ADI")
      (description "No Description Available")
      (libsource (lib "OP484FPZ") (part "OP484FPZ"))
    )
    (comp (ref "U4")
      (value "OP484FPZ")
      (footprint "N_14_ADI")
      (description "No Description Available")
      (libsource (lib "OP484FPZ") (part "OP484FPZ"))
    )
  )
  (nets
    (net (code "1") (name "/+3.3V") (class "Default")
      (node (ref "C11") (pin "2") (pinfunction "2_2") (pintype "passive"))
      (node (ref "C13") (pin "2") (pinfunction "2_2") (pintype "passive"))
      (node (ref "C15") (pin "2") (pinfunction "2_2") (pintype "passive"))
      (node (ref "C2") (pin "2") (pinfunction "2_2") (pintype "passive"))
      (node (ref "C4") (pin "2") (pinfunction "2_2") (pintype "passive"))
      (node (ref "C9") (pin "2") (pinfunction "2_2") (pintype "passive"))
      (node (ref "IC1") (pin "8") (pinfunction "VDD_8") (pintype "passive"))
      (node (ref "IC3") (pin "8") (pinfunction "VDD_8") (pintype "passive"))
      (node (ref "IC4") (pin "8") (pinfunction "VDD_8") (pintype "passive"))
      (node (ref "IC5") (pin "8") (pinfunction "VDD_8") (pintype "passive"))
      (node (ref "IC6") (pin "8") (pinfunction "VDD_8") (pintype "passive"))
      (node (ref "J1") (pin "1") (pinfunction "1_1") (pintype "passive"))
      (node (ref "J11") (pin "1") (pinfunction "1_1") (pintype "passive"))
      (node (ref "R22") (pin "1") (pinfunction "1_1") (pintype "passive"))
      (node (ref "R28") (pin "1") (pinfunction "1_1") (pintype "passive"))
      (node (ref "R29") (pin "1") (pinfunction "1_1") (pintype "passive"))
      (node (ref "U1") (pin "8") (pinfunction "V+_8") (pintype "power_in"))
      (node (ref "U2") (pin "3") (pinfunction "+VOUT_3") (pintype "passive"))
      (node (ref "U3") (pin "4") (pinfunction "V+_4") (pintype "power_in"))
      (node (ref "U4") (pin "4") (pinfunction "V+_4") (pintype "power_in"))
    )
    (net (code "2") (name "/+12V") (class "Default")
      (node (ref "C5") (pin "1") (pinfunction "1_1") (pintype "passive"))
      (node (ref "IC2") (pin "4") (pinfunction "VDD+_4") (pintype "passive"))
      (node (ref "IC7") (pin "4") (pinfunction "VDD+_4") (pintype "passive"))
      (node (ref "IC8") (pin "4") (pinfunction "VDD+_4") (pintype "passive"))
      (node (ref "IC9") (pin "4") (pinfunction "VDD+_4") (pintype "passive"))
      (node (ref "J30") (pin "1") (pinfunction "1_1") (pintype "passive"))
      (node (ref "P1") (pin "3") (pinfunction "Vout_3") (pintype "passive"))
    )
    (net (code "3") (name "/+12VDC") (class "Default")
      (node (ref "C1") (pin "1") (pinfunction "1_1") (pintype "passive"))
      (node (ref "C3") (pin "2") (pinfunction "2_2") (pintype "passive"))
      (node (ref "D1") (pin "2") (pinfunction "A_2") (pintype "passive"))
      (node (ref "J10") (pin "1") (pinfunction "1_1") (pintype "passive"))
      (node (ref "J12") (pin "1") (pinfunction "VBUS_1") (pintype "passive"))
      (node (ref "J13") (pin "1") (pinfunction "VBUS_1") (pintype "passive"))
      (node (ref "J14") (pin "1") (pinfunction "VBUS_1") (pintype "passive"))
      (node (ref "J40") (pin "14") (pinfunction "14_14") (pintype "passive"))
      (node (ref "J40") (pin "16") (pinfunction "16_16") (pintype "passive"))
      (node (ref "J7") (pin "1") (pinfunction "VBUS_1") (pintype "passive"))
      (node (ref "J8") (pin "1") (pinfunction "VBUS_1") (pintype "passive"))
      (node (ref "J9") (pin "1") (pinfunction "VBUS_1") (pintype "passive"))
      (node (ref "L1") (pin "2") (pinfunction "2_2") (pintype "passive"))
      (node (ref "P1") (pin "1") (pinfunction "Vin_1") (pintype "passive"))
      (node (ref "R32") (pin "1") (pinfunction "1_1") (pintype "passive"))
      (node (ref "SW1") (pin "2") (pinfunction "COM_2") (pintype "passive"))
    )
    (net (code "4") (name "/+EN") (class "Default")
      (node (ref "J39") (pin "1") (pinfunction "1_1") (pintype "passive"))
      (node (ref "J39") (pin "2") (pinfunction "2_2") (pintype "passive"))
      (node (ref "J39") (pin "3") (pinfunction "3_3") (pintype "passive"))
      (node (ref "J39") (pin "4") (pinfunction "4_4") (pintype "passive"))
      (node (ref "R25") (pin "1") (pinfunction "1_1") (pintype "passive"))
    )
    (net (code "5") (name "/+HT") (class "Default")
      (node (ref "J15") (pin "1") (pinfunction "1_1") (pintype "passive"))
      (node (ref "J15") (pin "2") (pinfunction "2_2") (pintype "passive"))
      (node (ref "J15") (pin "3") (pinfunction "3_3") (pintype "passive"))
      (node (ref "J15") (pin "4") (pinfunction "4_4") (pintype "passive"))
      (node (ref "R2") (pin "1") (pinfunction "1_1") (pintype "passive"))
    )
    (net (code "6") (name "/+HT2") (class "Default")
      (node (ref "J25") (pin "1") (pinfunction "1_1") (pintype "passive"))
      (node (ref "J25") (pin "2") (pinfunction "2_2") (pintype "passive"))
      (node (ref "J25") (pin "3") (pinfunction "3_3") (pintype "passive"))
      (node (ref "J25") (pin "4") (pinfunction "4_4") (pintype "passive"))
      (node (ref "R9") (pin "1") (pinfunction "1_1") (pintype "passive"))
    )
    (net (code "7") (name "/+HT3") (class "Default")
      (node (ref "J35") (pin "1") (pinfunction "1_1") (pintype "passive"))
      (node (ref "J35") (pin "2") (pinfunction "2_2") (pintype "passive"))
      (node (ref "J35") (pin "3") (pinfunction "3_3") (pintype "passive"))
      (node (ref "J35") (pin "4") (pinfunction "4_4") (pintype "passive"))
      (node (ref "R13") (pin "1") (pinfunction "1_1") (pintype "passive"))
    )
    (net (code "8") (name "/+HT4") (class "Default")
      (node (ref "J37") (pin "1") (pinfunction "1_1") (pintype "passive"))
      (node (ref "J37") (pin "2") (pinfunction "2_2") (pintype "passive"))
      (node (ref "J37") (pin "3") (pinfunction "3_3") (pintype "passive"))
      (node (ref "J37") (pin "4") (pinfunction "4_4") (pintype "passive"))
      (node (ref "R16") (pin "1") (pinfunction "1_1") (pintype "passive"))
    )
    (net (code "9") (name "/+T1") (class "Default")
      (node (ref "J33") (pin "1") (pinfunction "1_1") (pintype "passive"))
      (node (ref "J33") (pin "2") (pinfunction "2_2") (pintype "passive"))
      (node (ref "J33") (pin "3") (pinfunction "3_3") (pintype "passive"))
      (node (ref "J33") (pin "4") (pinfunction "4_4") (pintype "passive"))
      (node (ref "R24") (pin "2") (pinfunction "2_2") (pintype "passive"))
    )
    (net (code "10") (name "/-12V") (class "Default")
      (node (ref "C8") (pin "1") (pinfunction "1_1") (pintype "passive"))
      (node (ref "IC2") (pin "5") (pinfunction "VDD-_5") (pintype "passive"))
      (node (ref "IC7") (pin "5") (pinfunction "VDD-_5") (pintype "passive"))
      (node (ref "IC8") (pin "5") (pinfunction "VDD-_5") (pintype "passive"))
      (node (ref "IC9") (pin "5") (pinfunction "VDD-_5") (pintype "passive"))
      (node (ref "J29") (pin "1") (pinfunction "1_1") (pintype "passive"))
      (node (ref "P2") (pin "2") (pinfunction "GND_2") (pintype "passive"))
    )
    (net (code "11") (name "/-HT") (class "Default")
      (node (ref "IC2") (pin "1") (pinfunction "-HT_1") (pintype "passive"))
      (node (ref "J16") (pin "1") (pinfunction "1_1") (pintype "passive"))
      (node (ref "J16") (pin "2") (pinfunction "2_2") (pintype "passive"))
      (node (ref "J16") (pin "3") (pinfunction "3_3") (pintype "passive"))
      (node (ref "J16") (pin "4") (pinfunction "4_4") (pintype "passive"))
    )
    (net (code "12") (name "/-HT2") (class "Default")
      (node (ref "IC7") (pin "1") (pinfunction "-HT_1") (pintype "passive"))
      (node (ref "J26") (pin "1") (pinfunction "1_1") (pintype "passive"))
      (node (ref "J26") (pin "2") (pinfunction "2_2") (pintype "passive"))
      (node (ref "J26") (pin "3") (pinfunction "3_3") (pintype "passive"))
      (node (ref "J26") (pin "4") (pinfunction "4_4") (pintype "passive"))
    )
    (net (code "13") (name "/-HT3") (class "Default")
      (node (ref "IC8") (pin "1") (pinfunction "-HT_1") (pintype "passive"))
      (node (ref "J36") (pin "1") (pinfunction "1_1") (pintype "passive"))
      (node (ref "J36") (pin "2") (pinfunction "2_2") (pintype "passive"))
      (node (ref "J36") (pin "3") (pinfunction "3_3") (pintype "passive"))
      (node (ref "J36") (pin "4") (pinfunction "4_4") (pintype "passive"))
    )
    (net (code "14") (name "/-HT4") (class "Default")
      (node (ref "IC9") (pin "1") (pinfunction "-HT_1") (pintype "passive"))
      (node (ref "J38") (pin "1") (pinfunction "1_1") (pintype "passive"))
      (node (ref "J38") (pin "2") (pinfunction "2_2") (pintype "passive"))
      (node (ref "J38") (pin "3") (pinfunction "3_3") (pintype "passive"))
      (node (ref "J38") (pin "4") (pinfunction "4_4") (pintype "passive"))
    )
    (net (code "16") (name "/ADCINA0") (class "Default")
      (node (ref "J3") (pin "20") (pinfunction "20_20") (pintype "passive"))
    )
    (net (code "17") (name "/ADCINA3") (class "Default")
      (node (ref "J3") (pin "18") (pinfunction "18_18") (pintype "passive"))
    )
    (net (code "18") (name "/ADCINA5") (class "Default")
      (node (ref "J1") (pin "6") (pinfunction "6_6") (pintype "passive"))
      (node (ref "U3") (pin "1") (pinfunction "OUTA_1") (pintype "passive"))
      (node (ref "U3") (pin "2") (pinfunction "-INA_2") (pintype "passive"))
    )
    (net (code "19") (name "/ADCINA9") (class "Default")
      (node (ref "J1") (pin "18") (pinfunction "18_18") (pintype "passive"))
    )
    (net (code "20") (name "/ADCINB0") (class "Default")
      (node (ref "J1") (pin "8") (pinfunction "8_8") (pintype "passive"))
      (node (ref "U3") (pin "6") (pinfunction "-INB_6") (pintype "passive"))
      (node (ref "U3") (pin "7") (pinfunction "OUTB_7") (pintype "passive"))
    )
    (net (code "21") (name "/ADCINB1") (class "Default")
      (node (ref "J1") (pin "12") (pinfunction "12_12") (pintype "passive"))
      (node (ref "U3") (pin "8") (pinfunction "OUTC_8") (pintype "passive"))
      (node (ref "U3") (pin "9") (pinfunction "-INC_9") (pintype "passive"))
    )
    (net (code "22") (name "/ADCINB2") (class "Default")
      (node (ref "J1") (pin "14") (pinfunction "14_14") (pintype "passive"))
      (node (ref "U4") (pin "1") (pinfunction "OUTA_1") (pintype "passive"))
      (node (ref "U4") (pin "2") (pinfunction "-INA_2") (pintype "passive"))
    )
    (net (code "23") (name "/ADCINB6") (class "Default")
      (node (ref "C6") (pin "1") (pinfunction "1_1") (pintype "passive"))
      (node (ref "IC1") (pin "7") (pinfunction "VOUT_7") (pintype "passive"))
      (node (ref "J3") (pin "8") (pinfunction "8_8") (pintype "passive"))
    )
    (net (code "24") (name "/ADCINC0") (class "Default")
      (node (ref "J1") (pin "16") (pinfunction "16_16") (pintype "passive"))
      (node (ref "U4") (pin "13") (pinfunction "-IND_13") (pintype "passive"))
      (node (ref "U4") (pin "14") (pinfunction "OUTD_14") (pintype "passive"))
    )
    (net (code "25") (name "/ADCINC1") (class "Default")
      (node (ref "C12") (pin "1") (pinfunction "1_1") (pintype "passive"))
      (node (ref "IC5") (pin "7") (pinfunction "VOUT_7") (pintype "passive"))
      (node (ref "J3") (pin "12") (pinfunction "12_12") (pintype "passive"))
    )
    (net (code "26") (name "/ADCINC2") (class "Default")
      (node (ref "J1") (pin "10") (pinfunction "10_10") (pintype "passive"))
      (node (ref "U3") (pin "13") (pinfunction "-IND_13") (pintype "passive"))
      (node (ref "U3") (pin "14") (pinfunction "OUTD_14") (pintype "passive"))
    )
    (net (code "27") (name "/ADCINC3") (class "Default")
      (node (ref "C14") (pin "1") (pinfunction "1_1") (pintype "passive"))
      (node (ref "IC6") (pin "7") (pinfunction "VOUT_7") (pintype "passive"))
      (node (ref "J3") (pin "14") (pinfunction "14_14") (pintype "passive"))
    )
    (net (code "28") (name "/ADCINC5") (class "Default")
      (node (ref "C16") (pin "1") (pinfunction "1_1") (pintype "passive"))
      (node (ref "IC4") (pin "7") (pinfunction "VOUT_7") (pintype "passive"))
      (node (ref "J3") (pin "16") (pinfunction "16_16") (pintype "passive"))
    )
    (net (code "29") (name "/ADCINC14") (class "Default")
      (node (ref "C10") (pin "1") (pinfunction "1_1") (pintype "passive"))
      (node (ref "IC3") (pin "7") (pinfunction "VOUT_7") (pintype "passive"))
      (node (ref "J3") (pin "10") (pinfunction "10_10") (pintype "passive"))
    )
    (net (code "30") (name "/IP+") (class "Default")
      (node (ref "J5") (pin "1") (pinfunction "1_1") (pintype "passive"))
      (node (ref "J5") (pin "2") (pinfunction "2_2") (pintype "passive"))
      (node (ref "J5") (pin "3") (pinfunction "3_3") (pintype "passive"))
      (node (ref "J5") (pin "4") (pinfunction "4_4") (pintype "passive"))
      (node (ref "R1") (pin "1") (pinfunction "1_1") (pintype "passive"))
    )
    (net (code "31") (name "/IP+2") (class "Default")
      (node (ref "J17") (pin "1") (pinfunction "1_1") (pintype "passive"))
      (node (ref "J17") (pin "2") (pinfunction "2_2") (pintype "passive"))
      (node (ref "J17") (pin "3") (pinfunction "3_3") (pintype "passive"))
      (node (ref "J17") (pin "4") (pinfunction "4_4") (pintype "passive"))
      (node (ref "R5") (pin "1") (pinfunction "1_1") (pintype "passive"))
    )
    (net (code "32") (name "/IP+3") (class "Default")
      (node (ref "J19") (pin "1") (pinfunction "1_1") (pintype "passive"))
      (node (ref "J19") (pin "2") (pinfunction "2_2") (pintype "passive"))
      (node (ref "J19") (pin "3") (pinfunction "3_3") (pintype "passive"))
      (node (ref "J19") (pin "4") (pinfunction "4_4") (pintype "passive"))
      (node (ref "R7") (pin "1") (pinfunction "1_1") (pintype "passive"))
    )
    (net (code "33") (name "/IP+4") (class "Default")
      (node (ref "J21") (pin "1") (pinfunction "1_1") (pintype "passive"))
      (node (ref "J21") (pin "2") (pinfunction "2_2") (pintype "passive"))
      (node (ref "J21") (pin "3") (pinfunction "3_3") (pintype "passive"))
      (node (ref "J21") (pin "4") (pinfunction "4_4") (pintype "passive"))
      (node (ref "R8") (pin "1") (pinfunction "1_1") (pintype "passive"))
    )
    (net (code "34") (name "/IP+5") (class "Default")
      (node (ref "J23") (pin "1") (pinfunction "1_1") (pintype "passive"))
      (node (ref "J23") (pin "2") (pinfunction "2_2") (pintype "passive"))
      (node (ref "J23") (pin "3") (pinfunction "3_3") (pintype "passive"))
      (node (ref "J23") (pin "4") (pinfunction "4_4") (pintype "passive"))
      (node (ref "R6") (pin "1") (pinfunction "1_1") (pintype "passive"))
    )
    (net (code "35") (name "/IP-") (class "Default")
      (node (ref "IC1") (pin "3") (pinfunction "IP-_3") (pintype "passive"))
      (node (ref "IC1") (pin "4") (pinfunction "IP-_4") (pintype "passive"))
      (node (ref "J6") (pin "1") (pinfunction "1_1") (pintype "passive"))
      (node (ref "J6") (pin "2") (pinfunction "2_2") (pintype "passive"))
      (node (ref "J6") (pin "3") (pinfunction "3_3") (pintype "passive"))
      (node (ref "J6") (pin "4") (pinfunction "4_4") (pintype "passive"))
    )
    (net (code "36") (name "/IP-2") (class "Default")
      (node (ref "IC3") (pin "3") (pinfunction "IP-_3") (pintype "passive"))
      (node (ref "IC3") (pin "4") (pinfunction "IP-_4") (pintype "passive"))
      (node (ref "J18") (pin "1") (pinfunction "1_1") (pintype "passive"))
      (node (ref "J18") (pin "2") (pinfunction "2_2") (pintype "passive"))
      (node (ref "J18") (pin "3") (pinfunction "3_3") (pintype "passive"))
      (node (ref "J18") (pin "4") (pinfunction "4_4") (pintype "passive"))
    )
    (net (code "37") (name "/IP-3") (class "Default")
      (node (ref "IC5") (pin "3") (pinfunction "IP-_3") (pintype "passive"))
      (node (ref "IC5") (pin "4") (pinfunction "IP-_4") (pintype "passive"))
      (node (ref "J20") (pin "1") (pinfunction "1_1") (pintype "passive"))
      (node (ref "J20") (pin "2") (pinfunction "2_2") (pintype "passive"))
      (node (ref "J20") (pin "3") (pinfunction "3_3") (pintype "passive"))
      (node (ref "J20") (pin "4") (pinfunction "4_4") (pintype "passive"))
    )
    (net (code "38") (name "/IP-4") (class "Default")
      (node (ref "IC6") (pin "3") (pinfunction "IP-_3") (pintype "passive"))
      (node (ref "IC6") (pin "4") (pinfunction "IP-_4") (pintype "passive"))
      (node (ref "J22") (pin "1") (pinfunction "1_1") (pintype "passive"))
      (node (ref "J22") (pin "2") (pinfunction "2_2") (pintype "passive"))
      (node (ref "J22") (pin "3") (pinfunction "3_3") (pintype "passive"))
      (node (ref "J22") (pin "4") (pinfunction "4_4") (pintype "passive"))
    )
    (net (code "39") (name "/IP-5") (class "Default")
      (node (ref "IC4") (pin "3") (pinfunction "IP-_3") (pintype "passive"))
      (node (ref "IC4") (pin "4") (pinfunction "IP-_4") (pintype "passive"))
      (node (ref "J24") (pin "1") (pinfunction "1_1") (pintype "passive"))
      (node (ref "J24") (pin "2") (pinfunction "2_2") (pintype "passive"))
      (node (ref "J24") (pin "3") (pinfunction "3_3") (pintype "passive"))
      (node (ref "J24") (pin "4") (pinfunction "4_4") (pintype "passive"))
    )
    (net (code "40") (name "/OFFSET") (class "Default")
      (node (ref "R12") (pin "1") (pinfunction "1_1") (pintype "passive"))
      (node (ref "R15") (pin "1") (pinfunction "1_1") (pintype "passive"))
      (node (ref "R18") (pin "2") (pinfunction "2_2") (pintype "passive"))
      (node (ref "R19") (pin "2") (pinfunction "2_2") (pintype "passive"))
      (node (ref "U1") (pin "1") (pinfunction "OUTA_1") (pintype "passive"))
      (node (ref "U1") (pin "2") (pinfunction "-INA_2") (pintype "passive"))
    )
    (net (code "41") (name "/OFFSET-T") (class "Default")
      (node (ref "R26") (pin "1") (pinfunction "1_1") (pintype "passive"))
      (node (ref "U4") (pin "8") (pinfunction "OUTC_8") (pintype "passive"))
      (node (ref "U4") (pin "9") (pinfunction "-INC_9") (pintype "passive"))
    )
    (net (code "42") (name "/OFFSETEN") (class "Default")
      (node (ref "R27") (pin "1") (pinfunction "1_1") (pintype "passive"))
      (node (ref "U4") (pin "6") (pinfunction "-INB_6") (pintype "passive"))
      (node (ref "U4") (pin "7") (pinfunction "OUTB_7") (pintype "passive"))
    )
    (net (code "43") (name "/PWM1A") (class "Default")
      (node (ref "J12") (pin "2") (pinfunction "D-_2") (pintype "passive"))
      (node (ref "J4") (pin "1") (pinfunction "1_1") (pintype "passive"))
      (node (ref "J40") (pin "12") (pinfunction "12_12") (pintype "passive"))
    )
    (net (code "44") (name "/PWM1B") (class "Default")
      (node (ref "J12") (pin "3") (pinfunction "D+_3") (pintype "passive"))
      (node (ref "J4") (pin "3") (pinfunction "3_3") (pintype "passive"))
      (node (ref "J40") (pin "10") (pinfunction "10_10") (pintype "passive"))
    )
    (net (code "45") (name "/PWM2A") (class "Default")
      (node (ref "J14") (pin "2") (pinfunction "D-_2") (pintype "passive"))
      (node (ref "J4") (pin "9") (pinfunction "9_9") (pintype "passive"))
      (node (ref "J40") (pin "4") (pinfunction "4_4") (pintype "passive"))
    )
    (net (code "46") (name "/PWM2B") (class "Default")
      (node (ref "J14") (pin "3") (pinfunction "D+_3") (pintype "passive"))
      (node (ref "J4") (pin "11") (pinfunction "11_11") (pintype "passive"))
      (node (ref "J40") (pin "2") (pinfunction "2_2") (pintype "passive"))
    )
    (net (code "47") (name "/PWM3A") (class "Default")
      (node (ref "J2") (pin "9") (pinfunction "9_9") (pintype "passive"))
      (node (ref "J9") (pin "2") (pinfunction "D-_2") (pintype "passive"))
    )
    (net (code "48") (name "/PWM3B") (class "Default")
      (node (ref "J2") (pin "11") (pinfunction "11_11") (pintype "passive"))
      (node (ref "J9") (pin "3") (pinfunction "D+_3") (pintype "passive"))
    )
    (net (code "49") (name "/PWM4A") (class "Default")
      (node (ref "J13") (pin "2") (pinfunction "D-_2") (pintype "passive"))
      (node (ref "J4") (pin "5") (pinfunction "5_5") (pintype "passive"))
      (node (ref "J40") (pin "8") (pinfunction "8_8") (pintype "passive"))
    )
    (net (code "50") (name "/PWM4B") (class "Default")
      (node (ref "J13") (pin "3") (pinfunction "D+_3") (pintype "passive"))
      (node (ref "J4") (pin "7") (pinfunction "7_7") (pintype "passive"))
      (node (ref "J40") (pin "6") (pinfunction "6_6") (pintype "passive"))
    )
    (net (code "51") (name "/PWM5A") (class "Default")
      (node (ref "J2") (pin "5") (pinfunction "5_5") (pintype "passive"))
      (node (ref "J8") (pin "2") (pinfunction "D-_2") (pintype "passive"))
    )
    (net (code "52") (name "/PWM5B") (class "Default")
      (node (ref "J2") (pin "7") (pinfunction "7_7") (pintype "passive"))
      (node (ref "J8") (pin "3") (pinfunction "D+_3") (pintype "passive"))
    )
    (net (code "53") (name "/PWM6A") (class "Default")
      (node (ref "J2") (pin "1") (pinfunction "1_1") (pintype "passive"))
      (node (ref "J7") (pin "2") (pinfunction "D-_2") (pintype "passive"))
    )
    (net (code "54") (name "/PWM6B") (class "Default")
      (node (ref "J2") (pin "3") (pinfunction "3_3") (pintype "passive"))
      (node (ref "J7") (pin "3") (pinfunction "D+_3") (pintype "passive"))
    )
    (net (code "55") (name "/V1") (class "Default")
      (node (ref "IC2") (pin "3") (pinfunction "QV_3") (pintype "passive"))
      (node (ref "R10") (pin "1") (pinfunction "1_1") (pintype "passive"))
      (node (ref "R4") (pin "1") (pinfunction "1_1") (pintype "passive"))
    )
    (net (code "56") (name "/V2") (class "Default")
      (node (ref "IC7") (pin "3") (pinfunction "QV_3") (pintype "passive"))
      (node (ref "R11") (pin "1") (pinfunction "1_1") (pintype "passive"))
      (node (ref "R20") (pin "1") (pinfunction "1_1") (pintype "passive"))
    )
    (net (code "57") (name "/V3") (class "Default")
      (node (ref "IC8") (pin "3") (pinfunction "QV_3") (pintype "passive"))
      (node (ref "R14") (pin "1") (pinfunction "1_1") (pintype "passive"))
      (node (ref "R3") (pin "2") (pinfunction "2_2") (pintype "passive"))
    )
    (net (code "58") (name "/V4") (class "Default")
      (node (ref "IC9") (pin "3") (pinfunction "QV_3") (pintype "passive"))
      (node (ref "R17") (pin "1") (pinfunction "1_1") (pintype "passive"))
      (node (ref "R21") (pin "2") (pinfunction "2_2") (pintype "passive"))
    )
    (net (code "59") (name "GND") (class "Default")
      (node (ref "C1") (pin "2") (pinfunction "2_2") (pintype "passive"))
      (node (ref "C10") (pin "2") (pinfunction "2_2") (pintype "passive"))
      (node (ref "C11") (pin "1") (pinfunction "1_1") (pintype "passive"))
      (node (ref "C12") (pin "2") (pinfunction "2_2") (pintype "passive"))
      (node (ref "C13") (pin "1") (pinfunction "1_1") (pintype "passive"))
      (node (ref "C14") (pin "2") (pinfunction "2_2") (pintype "passive"))
      (node (ref "C15") (pin "1") (pinfunction "1_1") (pintype "passive"))
      (node (ref "C16") (pin "2") (pinfunction "2_2") (pintype "passive"))
      (node (ref "C2") (pin "1") (pinfunction "1_1") (pintype "passive"))
      (node (ref "C3") (pin "1") (pinfunction "1_1") (pintype "passive"))
      (node (ref "C4") (pin "1") (pinfunction "1_1") (pintype "passive"))
      (node (ref "C5") (pin "2") (pinfunction "2_2") (pintype "passive"))
      (node (ref "C6") (pin "2") (pinfunction "2_2") (pintype "passive"))
      (node (ref "C7") (pin "2") (pinfunction "2_2") (pintype "passive"))
      (node (ref "C8") (pin "2") (pinfunction "2_2") (pintype "passive"))
      (node (ref "C9") (pin "1") (pinfunction "1_1") (pintype "passive"))
      (node (ref "DS1") (pin "2") (pinfunction "K_2") (pintype "passive"))
      (node (ref "IC1") (pin "5") (pinfunction "GND_5") (pintype "passive"))
      (node (ref "IC3") (pin "5") (pinfunction "GND_5") (pintype "passive"))
      (node (ref "IC4") (pin "5") (pinfunction "GND_5") (pintype "passive"))
      (node (ref "IC5") (pin "5") (pinfunction "GND_5") (pintype "passive"))
      (node (ref "IC6") (pin "5") (pinfunction "GND_5") (pintype "passive"))
      (node (ref "J1") (pin "4") (pinfunction "4_4") (pintype "passive"))
      (node (ref "J12") (pin "4") (pinfunction "GND_4") (pintype "passive"))
      (node (ref "J13") (pin "4") (pinfunction "GND_4") (pintype "passive"))
      (node (ref "J14") (pin "4") (pinfunction "GND_4") (pintype "passive"))
      (node (ref "J2") (pin "2") (pinfunction "2_2") (pintype "passive"))
      (node (ref "J27") (pin "1") (pinfunction "1_1") (pintype "passive"))
      (node (ref "J28") (pin "1") (pinfunction "1_1") (pintype "passive"))
      (node (ref "J3") (pin "4") (pinfunction "4_4") (pintype "passive"))
      (node (ref "J31") (pin "1") (pinfunction "1_1") (pintype "passive"))
      (node (ref "J32") (pin "1") (pinfunction "1_1") (pintype "passive"))
      (node (ref "J34") (pin "2") (pinfunction "2_2") (pintype "passive"))
      (node (ref "J34") (pin "3") (pinfunction "3_3") (pintype "passive"))
      (node (ref "J4") (pin "2") (pinfunction "2_2") (pintype "passive"))
      (node (ref "J40") (pin "1") (pinfunction "1_1") (pintype "passive"))
      (node (ref "J40") (pin "11") (pinfunction "11_11") (pintype "passive"))
      (node (ref "J40") (pin "13") (pinfunction "13_13") (pintype "passive"))
      (node (ref "J40") (pin "15") (pinfunction "15_15") (pintype "passive"))
      (node (ref "J40") (pin "3") (pinfunction "3_3") (pintype "passive"))
      (node (ref "J40") (pin "5") (pinfunction "5_5") (pintype "passive"))
      (node (ref "J40") (pin "7") (pinfunction "7_7") (pintype "passive"))
      (node (ref "J40") (pin "9") (pinfunction "9_9") (pintype "passive"))
      (node (ref "J41") (pin "1") (pinfunction "1_1") (pintype "passive"))
      (node (ref "J41") (pin "2") (pinfunction "2_2") (pintype "passive"))
      (node (ref "J41") (pin "3") (pinfunction "3_3") (pintype "passive"))
      (node (ref "J41") (pin "4") (pinfunction "4_4") (pintype "passive"))
      (node (ref "J7") (pin "4") (pinfunction "GND_4") (pintype "passive"))
      (node (ref "J8") (pin "4") (pinfunction "GND_4") (pintype "passive"))
      (node (ref "J9") (pin "4") (pinfunction "GND_4") (pintype "passive"))
      (node (ref "P1") (pin "2") (pinfunction "GND_2") (pintype "passive"))
      (node (ref "P2") (pin "3") (pinfunction "Vout_3") (pintype "passive"))
      (node (ref "R11") (pin "2") (pinfunction "2_2") (pintype "passive"))
      (node (ref "R14") (pin "2") (pinfunction "2_2") (pintype "passive"))
      (node (ref "R17") (pin "2") (pinfunction "2_2") (pintype "passive"))
      (node (ref "R23") (pin "1") (pinfunction "1_1") (pintype "passive"))
      (node (ref "R30") (pin "1") (pinfunction "1_1") (pintype "passive"))
      (node (ref "R31") (pin "1") (pinfunction "1_1") (pintype "passive"))
      (node (ref "R4") (pin "2") (pinfunction "2_2") (pintype "passive"))
      (node (ref "SW1") (pin "1") (pinfunction "1_1") (pintype "passive"))
      (node (ref "U1") (pin "4") (pinfunction "V-_4") (pintype "power_in"))
      (node (ref "U2") (pin "2") (pinfunction "GND_2") (pintype "passive"))
      (node (ref "U3") (pin "11") (pinfunction "V-_11") (pintype "power_in"))
      (node (ref "U4") (pin "11") (pinfunction "V-_11") (pintype "power_in"))
    )
    (net (code "60") (name "GND_E") (class "Default")
      (node (ref "J12") (pin "5") (pinfunction "SHLD1_5") (pintype "passive"))
      (node (ref "J12") (pin "6") (pinfunction "SHLD2_6") (pintype "passive"))
      (node (ref "J13") (pin "5") (pinfunction "SHLD1_5") (pintype "passive"))
      (node (ref "J13") (pin "6") (pinfunction "SHLD2_6") (pintype "passive"))
      (node (ref "J14") (pin "5") (pinfunction "SHLD1_5") (pintype "passive"))
      (node (ref "J14") (pin "6") (pinfunction "SHLD2_6") (pintype "passive"))
      (node (ref "J7") (pin "5") (pinfunction "SHLD1_5") (pintype "passive"))
      (node (ref "J7") (pin "6") (pinfunction "SHLD2_6") (pintype "passive"))
      (node (ref "J8") (pin "5") (pinfunction "SHLD1_5") (pintype "passive"))
      (node (ref "J8") (pin "6") (pinfunction "SHLD2_6") (pintype "passive"))
      (node (ref "J9") (pin "5") (pinfunction "SHLD1_5") (pintype "passive"))
      (node (ref "J9") (pin "6") (pinfunction "SHLD2_6") (pintype "passive"))
      (node (ref "U2") (pin "4") (pinfunction "CASE_4") (pintype "passive"))
      (node (ref "U2") (pin "5") (pinfunction "CASE_5") (pintype "passive"))
    )
    (net (code "61") (name "Net-(D1-C)") (class "Default")
      (node (ref "D1") (pin "1") (pinfunction "C_1") (pintype "passive"))
      (node (ref "U2") (pin "1") (pinfunction "+VIN_1") (pintype "passive"))
    )
    (net (code "62") (name "Net-(DS1-A)") (class "Default")
      (node (ref "DS1") (pin "1") (pinfunction "A_1") (pintype "passive"))
      (node (ref "R32") (pin "2") (pinfunction "2_2") (pintype "passive"))
    )
    (net (code "63") (name "Net-(IC1-IP+-Pad1)") (class "Default")
      (node (ref "IC1") (pin "1") (pinfunction "IP+_1") (pintype "passive"))
      (node (ref "IC1") (pin "2") (pinfunction "IP+_2") (pintype "passive"))
      (node (ref "R1") (pin "2") (pinfunction "2_2") (pintype "passive"))
    )
    (net (code "64") (name "Net-(IC2-+HT)") (class "Default")
      (node (ref "IC2") (pin "2") (pinfunction "+HT_2") (pintype "passive"))
      (node (ref "R2") (pin "2") (pinfunction "2_2") (pintype "passive"))
    )
    (net (code "65") (name "Net-(IC3-IP+-Pad1)") (class "Default")
      (node (ref "IC3") (pin "1") (pinfunction "IP+_1") (pintype "passive"))
      (node (ref "IC3") (pin "2") (pinfunction "IP+_2") (pintype "passive"))
      (node (ref "R5") (pin "2") (pinfunction "2_2") (pintype "passive"))
    )
    (net (code "66") (name "Net-(IC4-IP+-Pad1)") (class "Default")
      (node (ref "IC4") (pin "1") (pinfunction "IP+_1") (pintype "passive"))
      (node (ref "IC4") (pin "2") (pinfunction "IP+_2") (pintype "passive"))
      (node (ref "R6") (pin "2") (pinfunction "2_2") (pintype "passive"))
    )
    (net (code "67") (name "Net-(IC5-IP+-Pad1)") (class "Default")
      (node (ref "IC5") (pin "1") (pinfunction "IP+_1") (pintype "passive"))
      (node (ref "IC5") (pin "2") (pinfunction "IP+_2") (pintype "passive"))
      (node (ref "R7") (pin "2") (pinfunction "2_2") (pintype "passive"))
    )
    (net (code "68") (name "Net-(IC6-IP+-Pad1)") (class "Default")
      (node (ref "IC6") (pin "1") (pinfunction "IP+_1") (pintype "passive"))
      (node (ref "IC6") (pin "2") (pinfunction "IP+_2") (pintype "passive"))
      (node (ref "R8") (pin "2") (pinfunction "2_2") (pintype "passive"))
    )
    (net (code "69") (name "Net-(IC7-+HT)") (class "Default")
      (node (ref "IC7") (pin "2") (pinfunction "+HT_2") (pintype "passive"))
      (node (ref "R9") (pin "2") (pinfunction "2_2") (pintype "passive"))
    )
    (net (code "70") (name "Net-(IC8-+HT)") (class "Default")
      (node (ref "IC8") (pin "2") (pinfunction "+HT_2") (pintype "passive"))
      (node (ref "R13") (pin "2") (pinfunction "2_2") (pintype "passive"))
    )
    (net (code "71") (name "Net-(IC9-+HT)") (class "Default")
      (node (ref "IC9") (pin "2") (pinfunction "+HT_2") (pintype "passive"))
      (node (ref "R16") (pin "2") (pinfunction "2_2") (pintype "passive"))
    )
    (net (code "72") (name "Net-(J34-Pad1)") (class "Default")
      (node (ref "J34") (pin "1") (pinfunction "1_1") (pintype "passive"))
      (node (ref "SW1") (pin "3") (pinfunction "3_3") (pintype "passive"))
    )
    (net (code "73") (name "Net-(P2-Vin)") (class "Default")
      (node (ref "C7") (pin "1") (pinfunction "1_1") (pintype "passive"))
      (node (ref "L1") (pin "1") (pinfunction "1_1") (pintype "passive"))
      (node (ref "P2") (pin "1") (pinfunction "Vin_1") (pintype "passive"))
    )
    (net (code "74") (name "Net-(U1-+INA)") (class "Default")
      (node (ref "R22") (pin "2") (pinfunction "2_2") (pintype "passive"))
      (node (ref "R23") (pin "2") (pinfunction "2_2") (pintype "passive"))
      (node (ref "U1") (pin "3") (pinfunction "+INA_3") (pintype "passive"))
    )
    (net (code "75") (name "Net-(U3-+INA)") (class "Default")
      (node (ref "R10") (pin "2") (pinfunction "2_2") (pintype "passive"))
      (node (ref "R15") (pin "2") (pinfunction "2_2") (pintype "passive"))
      (node (ref "U3") (pin "3") (pinfunction "+INA_3") (pintype "passive"))
    )
    (net (code "76") (name "Net-(U3-+INB)") (class "Default")
      (node (ref "R18") (pin "1") (pinfunction "1_1") (pintype "passive"))
      (node (ref "R20") (pin "2") (pinfunction "2_2") (pintype "passive"))
      (node (ref "U3") (pin "5") (pinfunction "+INB_5") (pintype "passive"))
    )
    (net (code "77") (name "Net-(U3-+INC)") (class "Default")
      (node (ref "R19") (pin "1") (pinfunction "1_1") (pintype "passive"))
      (node (ref "R21") (pin "1") (pinfunction "1_1") (pintype "passive"))
      (node (ref "U3") (pin "10") (pinfunction "+INC_10") (pintype "passive"))
    )
    (net (code "78") (name "Net-(U3-+IND)") (class "Default")
      (node (ref "R12") (pin "2") (pinfunction "2_2") (pintype "passive"))
      (node (ref "R3") (pin "1") (pinfunction "1_1") (pintype "passive"))
      (node (ref "U3") (pin "12") (pinfunction "+IND_12") (pintype "passive"))
    )
    (net (code "79") (name "Net-(U4-+INA)") (class "Default")
      (node (ref "R25") (pin "2") (pinfunction "2_2") (pintype "passive"))
      (node (ref "R27") (pin "2") (pinfunction "2_2") (pintype "passive"))
      (node (ref "U4") (pin "3") (pinfunction "+INA_3") (pintype "passive"))
    )
    (net (code "80") (name "Net-(U4-+INB)") (class "Default")
      (node (ref "R28") (pin "2") (pinfunction "2_2") (pintype "passive"))
      (node (ref "R30") (pin "2") (pinfunction "2_2") (pintype "passive"))
      (node (ref "U4") (pin "5") (pinfunction "+INB_5") (pintype "passive"))
    )
    (net (code "81") (name "Net-(U4-+INC)") (class "Default")
      (node (ref "R29") (pin "2") (pinfunction "2_2") (pintype "passive"))
      (node (ref "R31") (pin "2") (pinfunction "2_2") (pintype "passive"))
      (node (ref "U4") (pin "10") (pinfunction "+INC_10") (pintype "passive"))
    )
    (net (code "82") (name "Net-(U4-+IND)") (class "Default")
      (node (ref "R24") (pin "1") (pinfunction "1_1") (pintype "passive"))
      (node (ref "R26") (pin "2") (pinfunction "2_2") (pintype "passive"))
      (node (ref "U4") (pin "12") (pinfunction "+IND_12") (pintype "passive"))
    )
    (net (code "83") (name "unconnected-(IC1-VREF-Pad6)") (class "Default")
      (node (ref "IC1") (pin "6") (pinfunction "VREF_6") (pintype "passive"))
    )
    (net (code "84") (name "unconnected-(IC3-VREF-Pad6)") (class "Default")
      (node (ref "IC3") (pin "6") (pinfunction "VREF_6") (pintype "passive"))
    )
    (net (code "85") (name "unconnected-(IC4-VREF-Pad6)") (class "Default")
      (node (ref "IC4") (pin "6") (pinfunction "VREF_6") (pintype "passive"))
    )
    (net (code "86") (name "unconnected-(IC5-VREF-Pad6)") (class "Default")
      (node (ref "IC5") (pin "6") (pinfunction "VREF_6") (pintype "passive"))
    )
    (net (code "87") (name "unconnected-(IC6-VREF-Pad6)") (class "Default")
      (node (ref "IC6") (pin "6") (pinfunction "VREF_6") (pintype "passive"))
    )
    (net (code "88") (name "unconnected-(J1-Pad2)") (class "Default")
      (node (ref "J1") (pin "2") (pinfunction "2_2") (pintype "passive"))
    )
    (net (code "89") (name "unconnected-(J1-Pad3)") (class "Default")
      (node (ref "J1") (pin "3") (pinfunction "3_3") (pintype "passive"))
    )
    (net (code "90") (name "unconnected-(J1-Pad5)") (class "Default")
      (node (ref "J1") (pin "5") (pinfunction "5_5") (pintype "passive"))
    )
    (net (code "91") (name "unconnected-(J1-Pad7)") (class "Default")
      (node (ref "J1") (pin "7") (pinfunction "7_7") (pintype "passive"))
    )
    (net (code "92") (name "unconnected-(J1-Pad9)") (class "Default")
      (node (ref "J1") (pin "9") (pinfunction "9_9") (pintype "passive"))
    )
    (net (code "93") (name "unconnected-(J1-Pad11)") (class "Default")
      (node (ref "J1") (pin "11") (pinfunction "11_11") (pintype "passive"))
    )
    (net (code "94") (name "unconnected-(J1-Pad13)") (class "Default")
      (node (ref "J1") (pin "13") (pinfunction "13_13") (pintype "passive"))
    )
    (net (code "95") (name "unconnected-(J1-Pad15)") (class "Default")
      (node (ref "J1") (pin "15") (pinfunction "15_15") (pintype "passive"))
    )
    (net (code "96") (name "unconnected-(J1-Pad17)") (class "Default")
      (node (ref "J1") (pin "17") (pinfunction "17_17") (pintype "passive"))
    )
    (net (code "97") (name "unconnected-(J1-Pad19)") (class "Default")
      (node (ref "J1") (pin "19") (pinfunction "19_19") (pintype "passive"))
    )
    (net (code "98") (name "unconnected-(J1-Pad20)") (class "Default")
      (node (ref "J1") (pin "20") (pinfunction "20_20") (pintype "passive"))
    )
    (net (code "99") (name "unconnected-(J2-Pad4)") (class "Default")
      (node (ref "J2") (pin "4") (pinfunction "4_4") (pintype "passive"))
    )
    (net (code "100") (name "unconnected-(J2-Pad6)") (class "Default")
      (node (ref "J2") (pin "6") (pinfunction "6_6") (pintype "passive"))
    )
    (net (code "101") (name "unconnected-(J2-Pad8)") (class "Default")
      (node (ref "J2") (pin "8") (pinfunction "8_8") (pintype "passive"))
    )
    (net (code "102") (name "unconnected-(J2-Pad10)") (class "Default")
      (node (ref "J2") (pin "10") (pinfunction "10_10") (pintype "passive"))
    )
    (net (code "103") (name "unconnected-(J2-Pad12)") (class "Default")
      (node (ref "J2") (pin "12") (pinfunction "12_12") (pintype "passive"))
    )
    (net (code "104") (name "unconnected-(J2-Pad13)") (class "Default")
      (node (ref "J2") (pin "13") (pinfunction "13_13") (pintype "passive"))
    )
    (net (code "105") (name "unconnected-(J2-Pad14)") (class "Default")
      (node (ref "J2") (pin "14") (pinfunction "14_14") (pintype "passive"))
    )
    (net (code "106") (name "unconnected-(J2-Pad15)") (class "Default")
      (node (ref "J2") (pin "15") (pinfunction "15_15") (pintype "passive"))
    )
    (net (code "107") (name "unconnected-(J2-Pad16)") (class "Default")
      (node (ref "J2") (pin "16") (pinfunction "16_16") (pintype "passive"))
    )
    (net (code "108") (name "unconnected-(J2-Pad17)") (class "Default")
      (node (ref "J2") (pin "17") (pinfunction "17_17") (pintype "passive"))
    )
    (net (code "109") (name "unconnected-(J2-Pad18)") (class "Default")
      (node (ref "J2") (pin "18") (pinfunction "18_18") (pintype "passive"))
    )
    (net (code "110") (name "unconnected-(J2-Pad19)") (class "Default")
      (node (ref "J2") (pin "19") (pinfunction "19_19") (pintype "passive"))
    )
    (net (code "111") (name "unconnected-(J2-Pad20)") (class "Default")
      (node (ref "J2") (pin "20") (pinfunction "20_20") (pintype "passive"))
    )
    (net (code "112") (name "unconnected-(J3-Pad1)") (class "Default")
      (node (ref "J3") (pin "1") (pinfunction "1_1") (pintype "passive"))
    )
    (net (code "113") (name "unconnected-(J3-Pad2)") (class "Default")
      (node (ref "J3") (pin "2") (pinfunction "2_2") (pintype "passive"))
    )
    (net (code "114") (name "unconnected-(J3-Pad3)") (class "Default")
      (node (ref "J3") (pin "3") (pinfunction "3_3") (pintype "passive"))
    )
    (net (code "115") (name "unconnected-(J3-Pad5)") (class "Default")
      (node (ref "J3") (pin "5") (pinfunction "5_5") (pintype "passive"))
    )
    (net (code "116") (name "unconnected-(J3-Pad6)") (class "Default")
      (node (ref "J3") (pin "6") (pinfunction "6_6") (pintype "passive"))
    )
    (net (code "117") (name "unconnected-(J3-Pad7)") (class "Default")
      (node (ref "J3") (pin "7") (pinfunction "7_7") (pintype "passive"))
    )
    (net (code "118") (name "unconnected-(J3-Pad9)") (class "Default")
      (node (ref "J3") (pin "9") (pinfunction "9_9") (pintype "passive"))
    )
    (net (code "119") (name "unconnected-(J3-Pad11)") (class "Default")
      (node (ref "J3") (pin "11") (pinfunction "11_11") (pintype "passive"))
    )
    (net (code "120") (name "unconnected-(J3-Pad13)") (class "Default")
      (node (ref "J3") (pin "13") (pinfunction "13_13") (pintype "passive"))
    )
    (net (code "121") (name "unconnected-(J3-Pad15)") (class "Default")
      (node (ref "J3") (pin "15") (pinfunction "15_15") (pintype "passive"))
    )
    (net (code "122") (name "unconnected-(J3-Pad17)") (class "Default")
      (node (ref "J3") (pin "17") (pinfunction "17_17") (pintype "passive"))
    )
    (net (code "123") (name "unconnected-(J3-Pad19)") (class "Default")
      (node (ref "J3") (pin "19") (pinfunction "19_19") (pintype "passive"))
    )
    (net (code "124") (name "unconnected-(J4-Pad4)") (class "Default")
      (node (ref "J4") (pin "4") (pinfunction "4_4") (pintype "passive"))
    )
    (net (code "125") (name "unconnected-(J4-Pad6)") (class "Default")
      (node (ref "J4") (pin "6") (pinfunction "6_6") (pintype "passive"))
    )
    (net (code "126") (name "unconnected-(J4-Pad8)") (class "Default")
      (node (ref "J4") (pin "8") (pinfunction "8_8") (pintype "passive"))
    )
    (net (code "127") (name "unconnected-(J4-Pad10)") (class "Default")
      (node (ref "J4") (pin "10") (pinfunction "10_10") (pintype "passive"))
    )
    (net (code "128") (name "unconnected-(J4-Pad12)") (class "Default")
      (node (ref "J4") (pin "12") (pinfunction "12_12") (pintype "passive"))
    )
    (net (code "129") (name "unconnected-(J4-Pad13)") (class "Default")
      (node (ref "J4") (pin "13") (pinfunction "13_13") (pintype "passive"))
    )
    (net (code "130") (name "unconnected-(J4-Pad14)") (class "Default")
      (node (ref "J4") (pin "14") (pinfunction "14_14") (pintype "passive"))
    )
    (net (code "131") (name "unconnected-(J4-Pad15)") (class "Default")
      (node (ref "J4") (pin "15") (pinfunction "15_15") (pintype "passive"))
    )
    (net (code "132") (name "unconnected-(J4-Pad16)") (class "Default")
      (node (ref "J4") (pin "16") (pinfunction "16_16") (pintype "passive"))
    )
    (net (code "133") (name "unconnected-(J4-Pad17)") (class "Default")
      (node (ref "J4") (pin "17") (pinfunction "17_17") (pintype "passive"))
    )
    (net (code "134") (name "unconnected-(J4-Pad18)") (class "Default")
      (node (ref "J4") (pin "18") (pinfunction "18_18") (pintype "passive"))
    )
    (net (code "135") (name "unconnected-(J4-Pad19)") (class "Default")
      (node (ref "J4") (pin "19") (pinfunction "19_19") (pintype "passive"))
    )
    (net (code "136") (name "unconnected-(J4-Pad20)") (class "Default")
      (node (ref "J4") (pin "20") (pinfunction "20_20") (pintype "passive"))
    )
    (net (code "137") (name "unconnected-(U1-+INB-Pad5)") (class "Default")
      (node (ref "U1") (pin "5") (pinfunction "+INB_5") (pintype "passive"))
    )
    (net (code "138") (name "unconnected-(U1--INB-Pad6)") (class "Default")
      (node (ref "U1") (pin "6") (pinfunction "-INB_6") (pintype "passive"))
    )
    (net (code "139") (name "unconnected-(U1-OUTB-Pad7)") (class "Default")
      (node (ref "U1") (pin "7") (pinfunction "OUTB_7") (pintype "passive"))
    )
  )
)
